# bbarduino.net
KiCad netlist of a schematic drawn in EAGLE
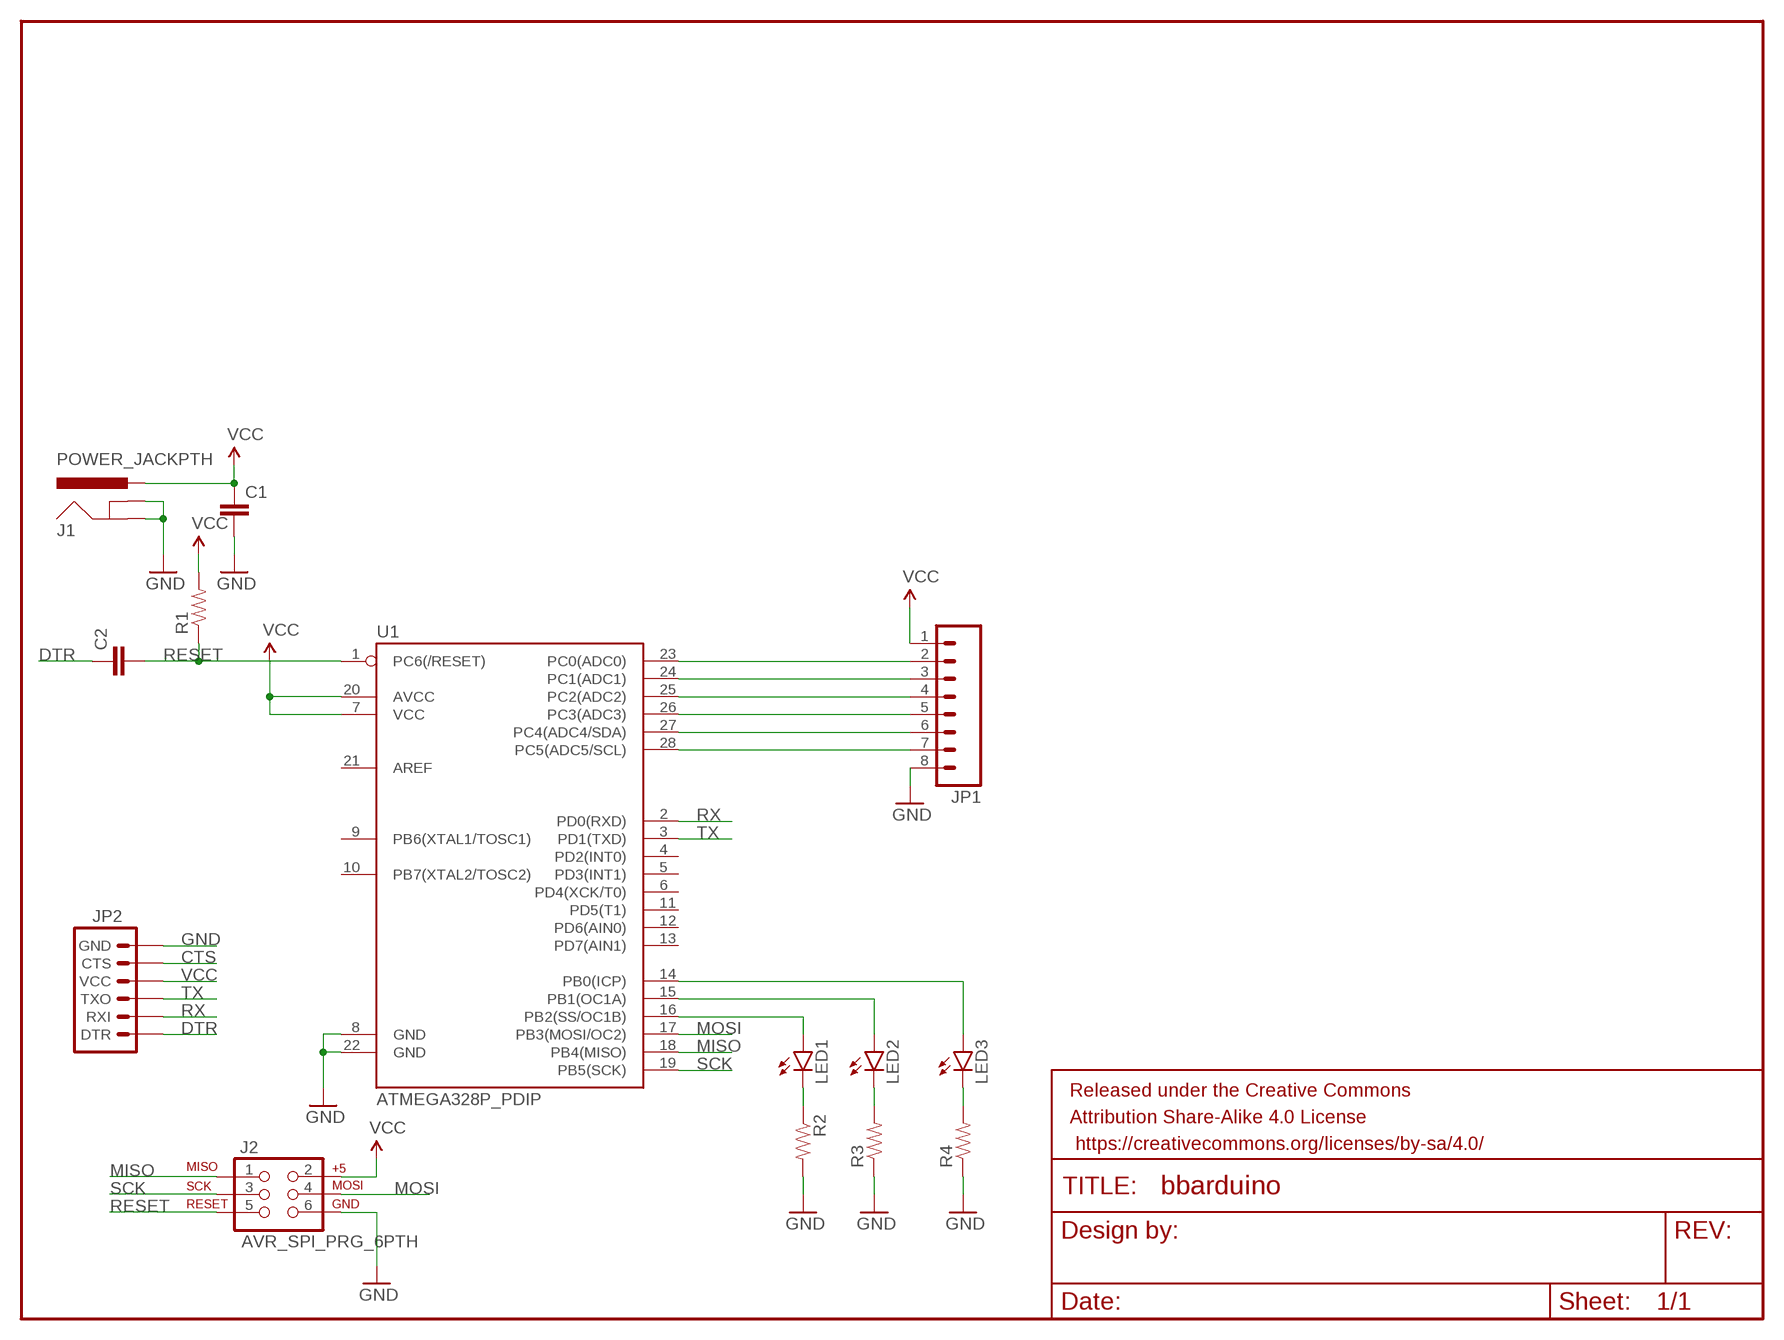
[diagram p0: schematic, sheet 1]

(export (version "E")
  (design (tool "Eeschema 10.0.6"))
  (components
    (comp (ref "C1")
      (value "CAPPTH")
      (footprint "eagle-import:CAP-PTH-SMALL")
      (libsource (lib "eagle-import") (part "SparkFun-Passives_CAPPTH"))
    )
    (comp (ref "C2")
      (value "CAPPTH")
      (footprint "eagle-import:CAP-PTH-SMALL")
      (libsource (lib "eagle-import") (part "CAPPTH"))
    )
    (comp (ref "FRAME1")
      (value "FRAME-LETTER")
      (footprint "eagle-import:CREATIVE_COMMONS")
      (libsource (lib "eagle-import") (part "FRAME-LETTER"))
    )
    (comp (ref "J1")
      (value "POWER_JACKPTH")
      (footprint "eagle-import:POWER_JACK_PTH")
      (libsource (lib "eagle-import") (part "POWER_JACKPTH"))
    )
    (comp (ref "J2")
      (value "AVR_SPI_PRG_6PTH")
      (footprint "eagle-import:2X3")
      (libsource (lib "eagle-import") (part "AVR_SPI_PRG_6PTH"))
    )
    (comp (ref "JP1")
      (value "M081X08")
      (footprint "eagle-import:1X08")
      (libsource (lib "eagle-import") (part "M081X08"))
    )
    (comp (ref "JP2")
      (value "ARDUINO_SERIAL_PROGRAMPTH")
      (footprint "eagle-import:1X06")
      (libsource (lib "eagle-import") (part "ARDUINO_SERIAL_PROGRAMPTH"))
    )
    (comp (ref "LED1")
      (value "LED5MM")
      (footprint "eagle-import:LED5MM")
      (libsource (lib "eagle-import") (part "LED5MM"))
    )
    (comp (ref "LED2")
      (value "LED5MM")
      (footprint "eagle-import:LED5MM")
      (libsource (lib "eagle-import") (part "LED5MM"))
    )
    (comp (ref "LED3")
      (value "LED5MM")
      (footprint "eagle-import:LED5MM")
      (libsource (lib "eagle-import") (part "LED5MM"))
    )
    (comp (ref "R1")
      (value "RESISTORPTH-1/4W")
      (footprint "eagle-import:AXIAL-0.4")
      (libsource (lib "eagle-import") (part "RESISTORPTH-1/4W"))
    )
    (comp (ref "R2")
      (value "RESISTORPTH-1/4W")
      (footprint "eagle-import:AXIAL-0.4")
      (libsource (lib "eagle-import") (part "RESISTORPTH-1/4W"))
    )
    (comp (ref "R3")
      (value "RESISTORPTH-1/4W")
      (footprint "eagle-import:AXIAL-0.4")
      (libsource (lib "eagle-import") (part "RESISTORPTH-1/4W"))
    )
    (comp (ref "R4")
      (value "RESISTORPTH-1/4W")
      (footprint "eagle-import:AXIAL-0.4")
      (libsource (lib "eagle-import") (part "RESISTORPTH-1/4W"))
    )
    (comp (ref "U1")
      (value "ATMEGA328P_PDIP")
      (footprint "eagle-import:DIL28-3")
      (libsource (lib "eagle-import") (part "ATMEGA328P_PDIP"))
    )
  )
  (nets
    (net (code "1") (name "/CTS") (class "Default")
      (node (ref "JP2") (pin "CTS") (pinfunction "CTS_CTS") (pintype "passive"))
    )
    (net (code "2") (name "/DTR") (class "Default")
      (node (ref "C2") (pin "1") (pinfunction "1_1") (pintype "passive"))
      (node (ref "JP2") (pin "DTR") (pinfunction "DTR_DTR") (pintype "passive"))
    )
    (net (code "3") (name "/MISO") (class "Default")
      (node (ref "J2") (pin "1") (pinfunction "1_1") (pintype "passive"))
      (node (ref "U1") (pin "18") (pinfunction "PB4(MISO)_18") (pintype "bidirectional"))
    )
    (net (code "4") (name "/MOSI") (class "Default")
      (node (ref "J2") (pin "4") (pinfunction "4_4") (pintype "passive"))
      (node (ref "U1") (pin "17") (pinfunction "PB3(MOSI/OC2)_17") (pintype "bidirectional"))
    )
    (net (code "5") (name "/RESET") (class "Default")
      (node (ref "C2") (pin "2") (pinfunction "2_2") (pintype "passive"))
      (node (ref "J2") (pin "5") (pinfunction "5_5") (pintype "passive"))
      (node (ref "R1") (pin "P$1") (pinfunction "1_P$1") (pintype "passive"))
      (node (ref "U1") (pin "1") (pinfunction "PC6(/RESET)_1") (pintype "bidirectional"))
    )
    (net (code "6") (name "/RX") (class "Default")
      (node (ref "JP2") (pin "RXI") (pinfunction "RXI_RXI") (pintype "passive"))
      (node (ref "U1") (pin "2") (pinfunction "PD0(RXD)_2") (pintype "bidirectional"))
    )
    (net (code "7") (name "/SCK") (class "Default")
      (node (ref "J2") (pin "3") (pinfunction "3_3") (pintype "passive"))
      (node (ref "U1") (pin "19") (pinfunction "PB5(SCK)_19") (pintype "bidirectional"))
    )
    (net (code "8") (name "/TX") (class "Default")
      (node (ref "JP2") (pin "TXO") (pinfunction "TXO_TXO") (pintype "passive"))
      (node (ref "U1") (pin "3") (pinfunction "PD1(TXD)_3") (pintype "bidirectional"))
    )
    (net (code "9") (name "GND") (class "Default")
      (node (ref "C1") (pin "2") (pinfunction "2_2") (pintype "passive"))
      (node (ref "J1") (pin "GND") (pinfunction "GND_GND") (pintype "bidirectional"))
      (node (ref "J1") (pin "GNDBREAK") (pinfunction "GNDBREAK_GNDBREAK") (pintype "bidirectional"))
      (node (ref "J2") (pin "6") (pinfunction "6_6") (pintype "passive"))
      (node (ref "JP1") (pin "8") (pinfunction "8_8") (pintype "passive"))
      (node (ref "JP2") (pin "GND") (pinfunction "GND_GND") (pintype "passive"))
      (node (ref "R2") (pin "P$2") (pinfunction "2_P$2") (pintype "passive"))
      (node (ref "R3") (pin "P$1") (pinfunction "1_P$1") (pintype "passive"))
      (node (ref "R4") (pin "P$1") (pinfunction "1_P$1") (pintype "passive"))
      (node (ref "U1") (pin "22") (pinfunction "GND_22") (pintype "bidirectional"))
      (node (ref "U1") (pin "8") (pinfunction "GND_8") (pintype "bidirectional"))
    )
    (net (code "10") (name "Net-(LED1-C)") (class "Default")
      (node (ref "LED1") (pin "K") (pinfunction "C_K") (pintype "passive"))
      (node (ref "R2") (pin "P$1") (pinfunction "1_P$1") (pintype "passive"))
    )
    (net (code "11") (name "Net-(LED2-C)") (class "Default")
      (node (ref "LED2") (pin "K") (pinfunction "C_K") (pintype "passive"))
      (node (ref "R3") (pin "P$2") (pinfunction "2_P$2") (pintype "passive"))
    )
    (net (code "12") (name "Net-(LED3-C)") (class "Default")
      (node (ref "LED3") (pin "K") (pinfunction "C_K") (pintype "passive"))
      (node (ref "R4") (pin "P$2") (pinfunction "2_P$2") (pintype "passive"))
    )
    (net (code "13") (name "Net-(U1-PB0(ICP))") (class "Default")
      (node (ref "LED3") (pin "A") (pinfunction "A_A") (pintype "passive"))
      (node (ref "U1") (pin "14") (pinfunction "PB0(ICP)_14") (pintype "bidirectional"))
    )
    (net (code "14") (name "Net-(U1-PB1(OC1A))") (class "Default")
      (node (ref "LED2") (pin "A") (pinfunction "A_A") (pintype "passive"))
      (node (ref "U1") (pin "15") (pinfunction "PB1(OC1A)_15") (pintype "bidirectional"))
    )
    (net (code "15") (name "Net-(U1-PB2(SS{slash}OC1B))") (class "Default")
      (node (ref "LED1") (pin "A") (pinfunction "A_A") (pintype "passive"))
      (node (ref "U1") (pin "16") (pinfunction "PB2(SS/OC1B)_16") (pintype "bidirectional"))
    )
    (net (code "16") (name "Net-(U1-PC0(ADC0))") (class "Default")
      (node (ref "JP1") (pin "2") (pinfunction "2_2") (pintype "passive"))
      (node (ref "U1") (pin "23") (pinfunction "PC0(ADC0)_23") (pintype "bidirectional"))
    )
    (net (code "17") (name "Net-(U1-PC1(ADC1))") (class "Default")
      (node (ref "JP1") (pin "3") (pinfunction "3_3") (pintype "passive"))
      (node (ref "U1") (pin "24") (pinfunction "PC1(ADC1)_24") (pintype "bidirectional"))
    )
    (net (code "18") (name "Net-(U1-PC2(ADC2))") (class "Default")
      (node (ref "JP1") (pin "4") (pinfunction "4_4") (pintype "passive"))
      (node (ref "U1") (pin "25") (pinfunction "PC2(ADC2)_25") (pintype "bidirectional"))
    )
    (net (code "19") (name "Net-(U1-PC3(ADC3))") (class "Default")
      (node (ref "JP1") (pin "5") (pinfunction "5_5") (pintype "passive"))
      (node (ref "U1") (pin "26") (pinfunction "PC3(ADC3)_26") (pintype "bidirectional"))
    )
    (net (code "20") (name "Net-(U1-PC4(ADC4{slash}SDA))") (class "Default")
      (node (ref "JP1") (pin "6") (pinfunction "6_6") (pintype "passive"))
      (node (ref "U1") (pin "27") (pinfunction "PC4(ADC4/SDA)_27") (pintype "bidirectional"))
    )
    (net (code "21") (name "Net-(U1-PC5(ADC5{slash}SCL))") (class "Default")
      (node (ref "JP1") (pin "7") (pinfunction "7_7") (pintype "passive"))
      (node (ref "U1") (pin "28") (pinfunction "PC5(ADC5/SCL)_28") (pintype "bidirectional"))
    )
    (net (code "22") (name "VCC") (class "Default")
      (node (ref "C1") (pin "1") (pinfunction "1_1") (pintype "passive"))
      (node (ref "J1") (pin "PWR") (pinfunction "PWR_PWR") (pintype "bidirectional"))
      (node (ref "J2") (pin "2") (pinfunction "2_2") (pintype "passive"))
      (node (ref "JP1") (pin "1") (pinfunction "1_1") (pintype "passive"))
      (node (ref "JP2") (pin "VCC") (pinfunction "VCC_VCC") (pintype "passive"))
      (node (ref "R1") (pin "P$2") (pinfunction "2_P$2") (pintype "passive"))
      (node (ref "U1") (pin "20") (pinfunction "AVCC_20") (pintype "bidirectional"))
      (node (ref "U1") (pin "7") (pinfunction "VCC_7") (pintype "bidirectional"))
    )
    (net (code "23") (name "unconnected-(U1-AREF-Pad21)") (class "Default")
      (node (ref "U1") (pin "21") (pinfunction "AREF_21") (pintype "bidirectional"))
    )
    (net (code "24") (name "unconnected-(U1-PB6(XTAL1{slash}TOSC1)-Pad9)") (class "Default")
      (node (ref "U1") (pin "9") (pinfunction "PB6(XTAL1/TOSC1)_9") (pintype "bidirectional"))
    )
    (net (code "25") (name "unconnected-(U1-PB7(XTAL2{slash}TOSC2)-Pad10)") (class "Default")
      (node (ref "U1") (pin "10") (pinfunction "PB7(XTAL2/TOSC2)_10") (pintype "bidirectional"))
    )
    (net (code "26") (name "unconnected-(U1-PD2(INT0)-Pad4)") (class "Default")
      (node (ref "U1") (pin "4") (pinfunction "PD2(INT0)_4") (pintype "bidirectional"))
    )
    (net (code "27") (name "unconnected-(U1-PD3(INT1)-Pad5)") (class "Default")
      (node (ref "U1") (pin "5") (pinfunction "PD3(INT1)_5") (pintype "bidirectional"))
    )
    (net (code "28") (name "unconnected-(U1-PD4(XCK{slash}T0)-Pad6)") (class "Default")
      (node (ref "U1") (pin "6") (pinfunction "PD4(XCK/T0)_6") (pintype "bidirectional"))
    )
    (net (code "29") (name "unconnected-(U1-PD5(T1)-Pad11)") (class "Default")
      (node (ref "U1") (pin "11") (pinfunction "PD5(T1)_11") (pintype "bidirectional"))
    )
    (net (code "30") (name "unconnected-(U1-PD6(AIN0)-Pad12)") (class "Default")
      (node (ref "U1") (pin "12") (pinfunction "PD6(AIN0)_12") (pintype "bidirectional"))
    )
    (net (code "31") (name "unconnected-(U1-PD7(AIN1)-Pad13)") (class "Default")
      (node (ref "U1") (pin "13") (pinfunction "PD7(AIN1)_13") (pintype "bidirectional"))
    )
  )
)
